# BISMILLAH_PCG.net
KiCad netlist of a schematic drawn in EAGLE
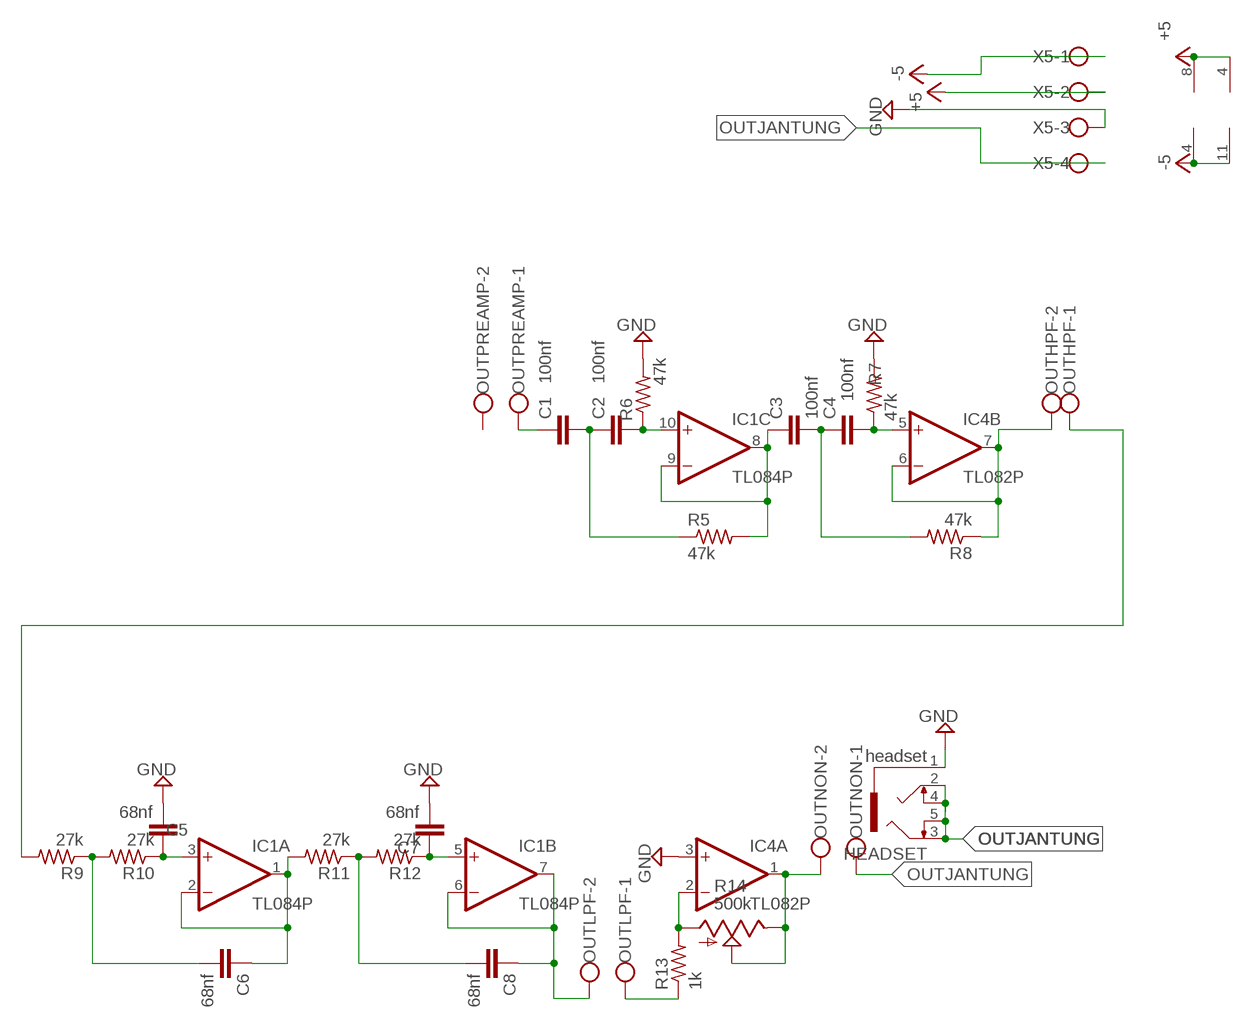
[diagram p0: schematic, sheet 1]

(export (version "E")
  (design (tool "Eeschema 10.0.6"))
  (components
    (comp (ref "C1")
      (value "100nf")
      (footprint "eagle-import:C050-025X075")
      (libsource (lib "eagle-import") (part "C-EU050-025X075"))
    )
    (comp (ref "C2")
      (value "100nf")
      (footprint "eagle-import:C050-025X075")
      (libsource (lib "eagle-import") (part "C-EU050-025X075"))
    )
    (comp (ref "C3")
      (value "100nf")
      (footprint "eagle-import:C050-025X075")
      (libsource (lib "eagle-import") (part "C-EU050-025X075"))
    )
    (comp (ref "C4")
      (value "100nf")
      (footprint "eagle-import:C050-025X075")
      (libsource (lib "eagle-import") (part "C-EU050-025X075"))
    )
    (comp (ref "C5")
      (value "68nf")
      (footprint "eagle-import:C050-025X075")
      (libsource (lib "eagle-import") (part "C-EU050-025X075"))
    )
    (comp (ref "C6")
      (value "68nf")
      (footprint "eagle-import:C050-025X075")
      (libsource (lib "eagle-import") (part "C-EU050-025X075"))
    )
    (comp (ref "C7")
      (value "68nf")
      (footprint "eagle-import:C050-025X075")
      (libsource (lib "eagle-import") (part "C-EU050-025X075"))
    )
    (comp (ref "C8")
      (value "68nf")
      (footprint "eagle-import:C050-025X075")
      (libsource (lib "eagle-import") (part "C-EU050-025X075"))
    )
    (comp (ref "HEADSET")
      (value "headset")
      (footprint "eagle-import:1503_09")
      (libsource (lib "eagle-import") (part "1503_09"))
    )
    (comp (ref "IC1")
      (value "TL084P")
      (footprint "eagle-import:DIL14")
      (libsource (lib "eagle-import") (part "TL084P"))
    )
    (comp (ref "IC4")
      (value "TL082P")
      (footprint "eagle-import:DIL08")
      (libsource (lib "eagle-import") (part "TL082P"))
    )
    (comp (ref "OUTHPF")
      (value "W237-102")
      (footprint "eagle-import:W237-102")
      (fields (field (name "MPN") "237-102"))
      (libsource (lib "eagle-import") (part "W237-102"))
    )
    (comp (ref "OUTLPF")
      (value "W237-102")
      (footprint "eagle-import:W237-102")
      (fields (field (name "MPN") "237-102"))
      (libsource (lib "eagle-import") (part "W237-102"))
    )
    (comp (ref "OUTNON")
      (value "W237-102")
      (footprint "eagle-import:W237-102")
      (fields (field (name "MPN") "237-102"))
      (libsource (lib "eagle-import") (part "W237-102"))
    )
    (comp (ref "OUTPREAMP")
      (value "W237-102")
      (footprint "eagle-import:W237-102")
      (fields (field (name "MPN") "237-102"))
      (libsource (lib "eagle-import") (part "W237-102"))
    )
    (comp (ref "R5")
      (value "47k")
      (footprint "eagle-import:0207_7")
      (libsource (lib "eagle-import") (part "R-US_0207/7"))
    )
    (comp (ref "R6")
      (value "47k")
      (footprint "eagle-import:0207_7")
      (libsource (lib "eagle-import") (part "R-US_0207/7"))
    )
    (comp (ref "R7")
      (value "47k")
      (footprint "eagle-import:0207_7")
      (libsource (lib "eagle-import") (part "R-US_0207/7"))
    )
    (comp (ref "R8")
      (value "47k")
      (footprint "eagle-import:0207_7")
      (libsource (lib "eagle-import") (part "R-US_0207/7"))
    )
    (comp (ref "R9")
      (value "27k")
      (footprint "eagle-import:0207_7")
      (libsource (lib "eagle-import") (part "R-US_0207/7"))
    )
    (comp (ref "R10")
      (value "27k")
      (footprint "eagle-import:0207_7")
      (libsource (lib "eagle-import") (part "R-US_0207/7"))
    )
    (comp (ref "R11")
      (value "27k")
      (footprint "eagle-import:0207_7")
      (libsource (lib "eagle-import") (part "R-US_0207/7"))
    )
    (comp (ref "R12")
      (value "27k")
      (footprint "eagle-import:0207_7")
      (libsource (lib "eagle-import") (part "R-US_0207/7"))
    )
    (comp (ref "R13")
      (value "1k")
      (footprint "eagle-import:0207_7")
      (libsource (lib "eagle-import") (part "R-US_0207/7"))
    )
    (comp (ref "R14")
      (value "500k")
      (footprint "eagle-import:B64Y")
      (libsource (lib "eagle-import") (part "TRIM_US-B64Y"))
    )
    (comp (ref "X5")
      (value "W237-4")
      (footprint "eagle-import:W237-4")
      (libsource (lib "eagle-import") (part "W237-4"))
    )
  )
  (nets
    (net (code "1") (name "+5") (class "Default")
      (node (ref "IC1") (pin "4") (pinfunction "V+_4") (pintype "power_in"))
      (node (ref "IC4") (pin "8") (pinfunction "V+_8") (pintype "power_in"))
      (node (ref "X5") (pin "2") (pinfunction "KL_2") (pintype "passive"))
    )
    (net (code "2") (name "-5") (class "Default")
      (node (ref "IC1") (pin "11") (pinfunction "V-_11") (pintype "power_in"))
      (node (ref "IC4") (pin "4") (pinfunction "V-_4") (pintype "power_in"))
      (node (ref "X5") (pin "1") (pinfunction "KL_1") (pintype "passive"))
    )
    (net (code "3") (name "GND") (class "Default")
      (node (ref "C5") (pin "2") (pinfunction "2_2") (pintype "passive"))
      (node (ref "C7") (pin "2") (pinfunction "2_2") (pintype "passive"))
      (node (ref "HEADSET") (pin "1") (pinfunction "1_1") (pintype "passive"))
      (node (ref "IC4") (pin "3") (pinfunction "+IN_3") (pintype "input"))
      (node (ref "R6") (pin "2") (pinfunction "2_2") (pintype "passive"))
      (node (ref "R7") (pin "2") (pinfunction "2_2") (pintype "passive"))
      (node (ref "X5") (pin "3") (pinfunction "KL_3") (pintype "passive"))
    )
    (net (code "4") (name "Net-(C1-Pad2)") (class "Default")
      (node (ref "C1") (pin "2") (pinfunction "2_2") (pintype "passive"))
      (node (ref "C2") (pin "1") (pinfunction "1_1") (pintype "passive"))
      (node (ref "R5") (pin "1") (pinfunction "1_1") (pintype "passive"))
    )
    (net (code "5") (name "Net-(C3-Pad2)") (class "Default")
      (node (ref "C3") (pin "2") (pinfunction "2_2") (pintype "passive"))
      (node (ref "C4") (pin "1") (pinfunction "1_1") (pintype "passive"))
      (node (ref "R8") (pin "2") (pinfunction "2_2") (pintype "passive"))
    )
    (net (code "6") (name "Net-(C6-Pad2)") (class "Default")
      (node (ref "C6") (pin "2") (pinfunction "2_2") (pintype "passive"))
      (node (ref "R10") (pin "2") (pinfunction "2_2") (pintype "passive"))
      (node (ref "R9") (pin "1") (pinfunction "1_1") (pintype "passive"))
    )
    (net (code "7") (name "Net-(C8-Pad2)") (class "Default")
      (node (ref "C8") (pin "2") (pinfunction "2_2") (pintype "passive"))
      (node (ref "R11") (pin "1") (pinfunction "1_1") (pintype "passive"))
      (node (ref "R12") (pin "2") (pinfunction "2_2") (pintype "passive"))
    )
    (net (code "8") (name "Net-(IC1A-+IN)") (class "Default")
      (node (ref "C5") (pin "1") (pinfunction "1_1") (pintype "passive"))
      (node (ref "IC1") (pin "3") (pinfunction "+IN_3") (pintype "input"))
      (node (ref "R10") (pin "1") (pinfunction "1_1") (pintype "passive"))
    )
    (net (code "9") (name "Net-(IC1A--IN)") (class "Default")
      (node (ref "C6") (pin "1") (pinfunction "1_1") (pintype "passive"))
      (node (ref "IC1") (pin "1") (pinfunction "OUT_1") (pintype "output"))
      (node (ref "IC1") (pin "2") (pinfunction "-IN_2") (pintype "input"))
      (node (ref "R11") (pin "2") (pinfunction "2_2") (pintype "passive"))
    )
    (net (code "10") (name "Net-(IC1B-+IN)") (class "Default")
      (node (ref "C7") (pin "1") (pinfunction "1_1") (pintype "passive"))
      (node (ref "IC1") (pin "5") (pinfunction "+IN_5") (pintype "input"))
      (node (ref "R12") (pin "1") (pinfunction "1_1") (pintype "passive"))
    )
    (net (code "11") (name "Net-(IC1B--IN)") (class "Default")
      (node (ref "C8") (pin "1") (pinfunction "1_1") (pintype "passive"))
      (node (ref "IC1") (pin "6") (pinfunction "-IN_6") (pintype "input"))
      (node (ref "IC1") (pin "7") (pinfunction "OUT_7") (pintype "output"))
      (node (ref "OUTLPF") (pin "2") (pinfunction "KL_2") (pintype "passive"))
    )
    (net (code "12") (name "Net-(IC1C-+IN)") (class "Default")
      (node (ref "C2") (pin "2") (pinfunction "2_2") (pintype "passive"))
      (node (ref "IC1") (pin "10") (pinfunction "+IN_10") (pintype "input"))
      (node (ref "R6") (pin "1") (pinfunction "1_1") (pintype "passive"))
    )
    (net (code "13") (name "Net-(IC1C--IN)") (class "Default")
      (node (ref "C3") (pin "1") (pinfunction "1_1") (pintype "passive"))
      (node (ref "IC1") (pin "8") (pinfunction "OUT_8") (pintype "output"))
      (node (ref "IC1") (pin "9") (pinfunction "-IN_9") (pintype "input"))
      (node (ref "R5") (pin "2") (pinfunction "2_2") (pintype "passive"))
    )
    (net (code "14") (name "Net-(IC4A--IN)") (class "Default")
      (node (ref "IC4") (pin "2") (pinfunction "-IN_2") (pintype "input"))
      (node (ref "R13") (pin "2") (pinfunction "2_2") (pintype "passive"))
      (node (ref "R14") (pin "A") (pinfunction "A_A") (pintype "passive"))
    )
    (net (code "15") (name "Net-(IC4A-OUT)") (class "Default")
      (node (ref "IC4") (pin "1") (pinfunction "OUT_1") (pintype "output"))
      (node (ref "OUTNON") (pin "2") (pinfunction "KL_2") (pintype "passive"))
      (node (ref "R14") (pin "E") (pinfunction "E_E") (pintype "passive"))
      (node (ref "R14") (pin "S") (pinfunction "S_S") (pintype "passive"))
    )
    (net (code "16") (name "Net-(IC4B-+IN)") (class "Default")
      (node (ref "C4") (pin "2") (pinfunction "2_2") (pintype "passive"))
      (node (ref "IC4") (pin "5") (pinfunction "+IN_5") (pintype "input"))
      (node (ref "R7") (pin "1") (pinfunction "1_1") (pintype "passive"))
    )
    (net (code "17") (name "Net-(IC4B--IN)") (class "Default")
      (node (ref "IC4") (pin "6") (pinfunction "-IN_6") (pintype "input"))
      (node (ref "IC4") (pin "7") (pinfunction "OUT_7") (pintype "output"))
      (node (ref "OUTHPF") (pin "2") (pinfunction "KL_2") (pintype "passive"))
      (node (ref "R8") (pin "1") (pinfunction "1_1") (pintype "passive"))
    )
    (net (code "18") (name "Net-(OUTHPFA-KL)") (class "Default")
      (node (ref "OUTHPF") (pin "1") (pinfunction "KL_1") (pintype "passive"))
      (node (ref "R9") (pin "2") (pinfunction "2_2") (pintype "passive"))
    )
    (net (code "19") (name "Net-(OUTLPFA-KL)") (class "Default")
      (node (ref "OUTLPF") (pin "1") (pinfunction "KL_1") (pintype "passive"))
      (node (ref "R13") (pin "1") (pinfunction "1_1") (pintype "passive"))
    )
    (net (code "20") (name "Net-(OUTPREAMPA-KL)") (class "Default")
      (node (ref "C1") (pin "1") (pinfunction "1_1") (pintype "passive"))
      (node (ref "OUTPREAMP") (pin "1") (pinfunction "KL_1") (pintype "passive"))
    )
    (net (code "21") (name "OUTJANTUNG") (class "Default")
      (node (ref "HEADSET") (pin "2") (pinfunction "2_2") (pintype "passive"))
      (node (ref "HEADSET") (pin "3") (pinfunction "3_3") (pintype "passive"))
      (node (ref "HEADSET") (pin "4") (pinfunction "4_4") (pintype "passive"))
      (node (ref "HEADSET") (pin "5") (pinfunction "5_5") (pintype "passive"))
      (node (ref "OUTNON") (pin "1") (pinfunction "KL_1") (pintype "passive"))
      (node (ref "X5") (pin "4") (pinfunction "KL_4") (pintype "passive"))
    )
    (net (code "22") (name "unconnected-(OUTPREAMPB-KL-Pad2)") (class "Default")
      (node (ref "OUTPREAMP") (pin "2") (pinfunction "KL_2") (pintype "passive"))
    )
  )
)
